# WattMeter_v4_I2C_Nov19_2018.net
KiCad netlist of a schematic drawn in EAGLE
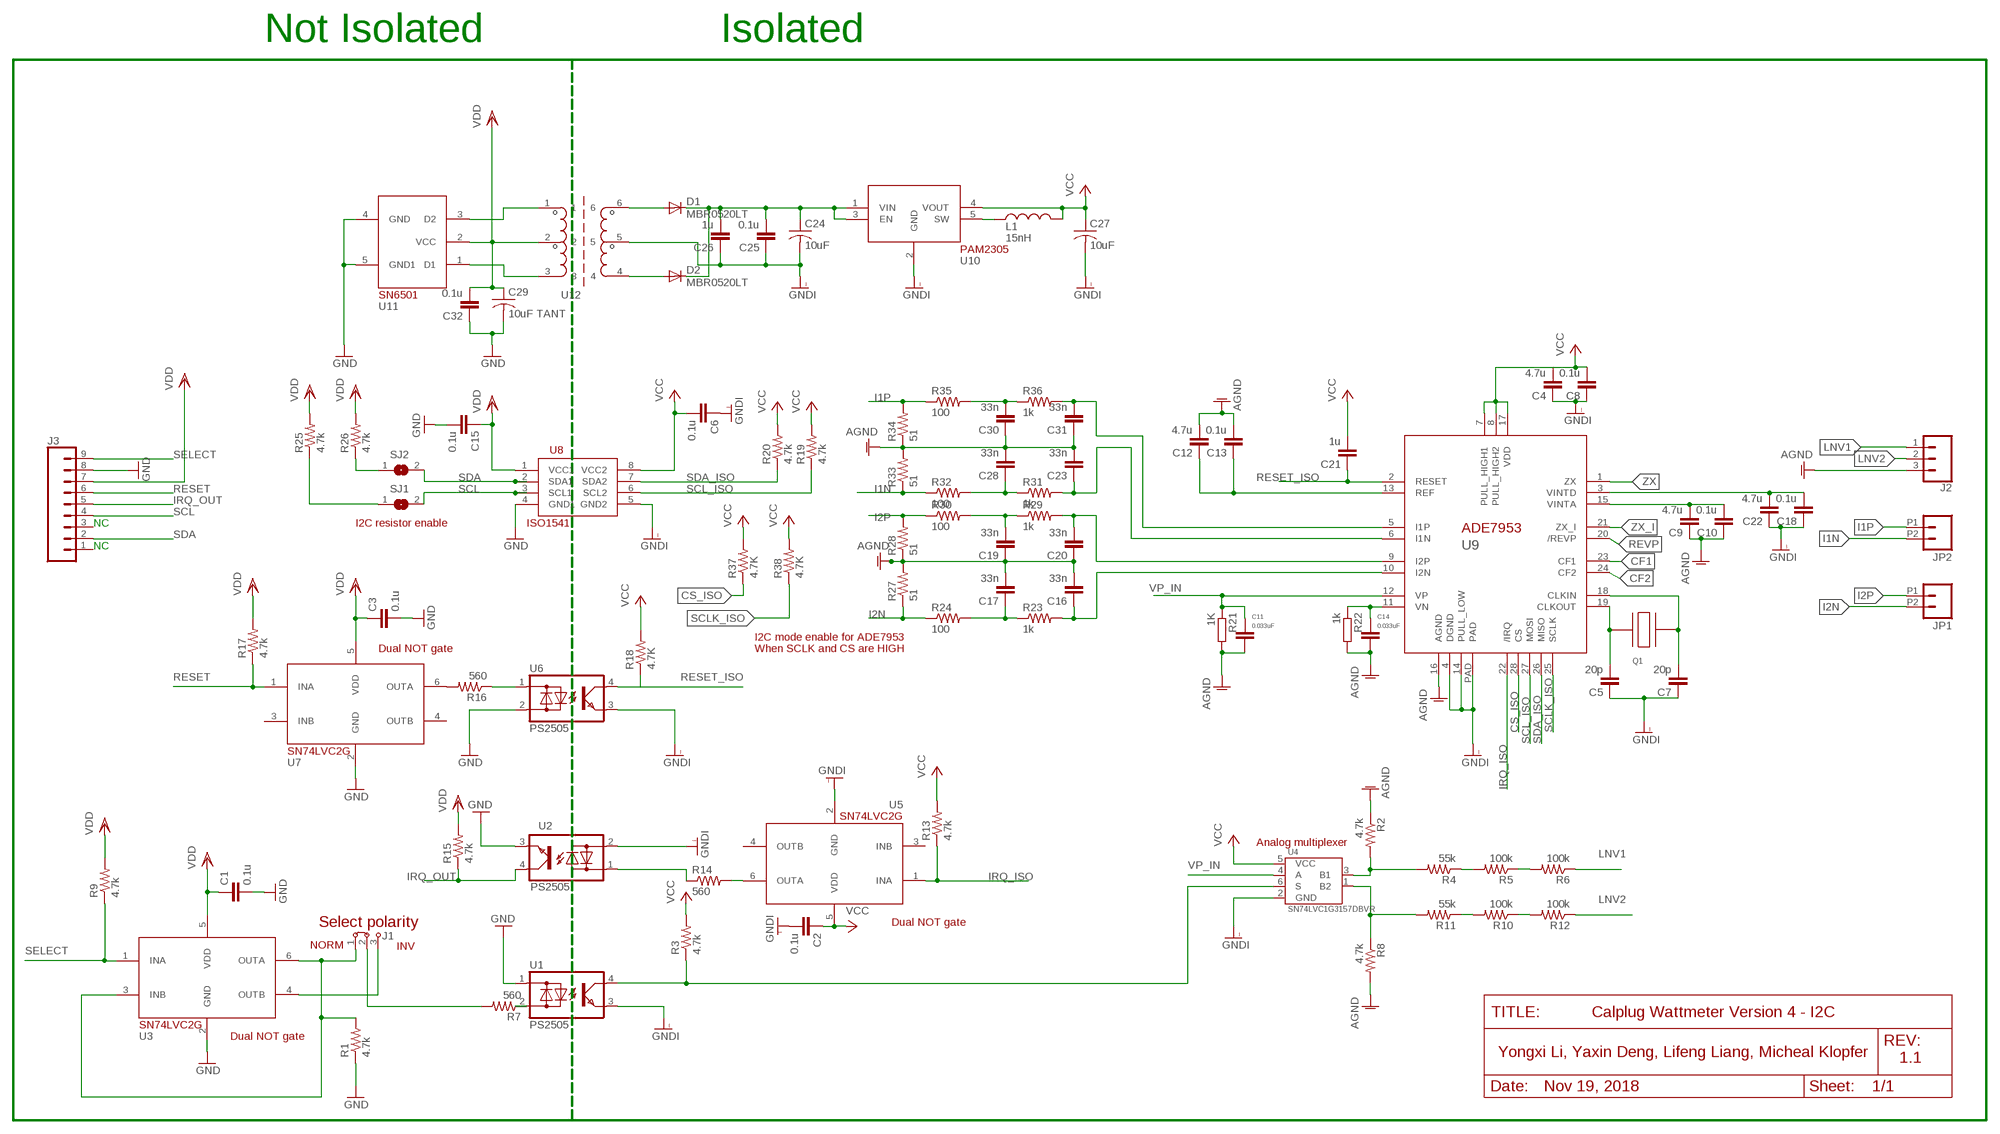
[diagram p0: schematic, sheet 1]

(export (version "E")
  (design (tool "Eeschema 10.0.6"))
  (components
    (comp (ref "C1")
      (value "0.1u")
      (footprint "eagle-import:0402-CAP")
      (libsource (lib "eagle-import") (part "0402-CAP"))
    )
    (comp (ref "C2")
      (value "0.1u")
      (footprint "eagle-import:0402-CAP")
      (libsource (lib "eagle-import") (part "0402-CAP"))
    )
    (comp (ref "C3")
      (value "0.1u")
      (footprint "eagle-import:0402-CAP")
      (libsource (lib "eagle-import") (part "0402-CAP"))
    )
    (comp (ref "C4")
      (value "4.7u")
      (footprint "eagle-import:0402-CAP")
      (libsource (lib "eagle-import") (part "0402-CAP"))
    )
    (comp (ref "C5")
      (value "20p")
      (footprint "eagle-import:0402-CAP")
      (libsource (lib "eagle-import") (part "0402-CAP"))
    )
    (comp (ref "C6")
      (value "0.1u")
      (footprint "eagle-import:0402-CAP")
      (libsource (lib "eagle-import") (part "0402-CAP"))
    )
    (comp (ref "C7")
      (value "20p")
      (footprint "eagle-import:0402-CAP")
      (libsource (lib "eagle-import") (part "0402-CAP"))
    )
    (comp (ref "C8")
      (value "0.1u")
      (footprint "eagle-import:0402-CAP")
      (libsource (lib "eagle-import") (part "0402-CAP"))
    )
    (comp (ref "C9")
      (value "4.7u")
      (footprint "eagle-import:0402-CAP")
      (libsource (lib "eagle-import") (part "0402-CAP"))
    )
    (comp (ref "C10")
      (value "0.1u")
      (footprint "eagle-import:0402-CAP")
      (libsource (lib "eagle-import") (part "0402-CAP"))
    )
    (comp (ref "C11")
      (value "0.033uF")
      (footprint "eagle-import:C0805K")
      (libsource (lib "eagle-import") (part "C-EUC0805K"))
    )
    (comp (ref "C12")
      (value "4.7u")
      (footprint "eagle-import:0402-CAP")
      (libsource (lib "eagle-import") (part "0402-CAP"))
    )
    (comp (ref "C13")
      (value "0.1u")
      (footprint "eagle-import:0402-CAP")
      (libsource (lib "eagle-import") (part "0402-CAP"))
    )
    (comp (ref "C14")
      (value "0.033uF")
      (footprint "eagle-import:C0805K")
      (libsource (lib "eagle-import") (part "C-EUC0805K"))
    )
    (comp (ref "C15")
      (value "0.1u")
      (footprint "eagle-import:0402-CAP")
      (libsource (lib "eagle-import") (part "0402-CAP"))
    )
    (comp (ref "C16")
      (value "33n")
      (footprint "eagle-import:0402-CAP")
      (libsource (lib "eagle-import") (part "0402-CAP"))
    )
    (comp (ref "C17")
      (value "33n")
      (footprint "eagle-import:0402-CAP")
      (libsource (lib "eagle-import") (part "0402-CAP"))
    )
    (comp (ref "C18")
      (value "0.1u")
      (footprint "eagle-import:0402-CAP")
      (libsource (lib "eagle-import") (part "0402-CAP"))
    )
    (comp (ref "C19")
      (value "33n")
      (footprint "eagle-import:0402-CAP")
      (libsource (lib "eagle-import") (part "0402-CAP"))
    )
    (comp (ref "C20")
      (value "33n")
      (footprint "eagle-import:0402-CAP")
      (libsource (lib "eagle-import") (part "0402-CAP"))
    )
    (comp (ref "C21")
      (value "1u")
      (footprint "eagle-import:0402-CAP")
      (libsource (lib "eagle-import") (part "0402-CAP"))
    )
    (comp (ref "C22")
      (value "4.7u")
      (footprint "eagle-import:0402-CAP")
      (libsource (lib "eagle-import") (part "0402-CAP"))
    )
    (comp (ref "C23")
      (value "33n")
      (footprint "eagle-import:0402-CAP")
      (libsource (lib "eagle-import") (part "0402-CAP"))
    )
    (comp (ref "C24")
      (value "10uF")
      (footprint "eagle-import:C0603")
      (libsource (lib "eagle-import") (part "C-USC0603"))
    )
    (comp (ref "C25")
      (value "0.1u")
      (footprint "eagle-import:0402-CAP")
      (libsource (lib "eagle-import") (part "0402-CAP"))
    )
    (comp (ref "C26")
      (value "1u")
      (footprint "eagle-import:0402-CAP")
      (libsource (lib "eagle-import") (part "0402-CAP"))
    )
    (comp (ref "C27")
      (value "10uF")
      (footprint "eagle-import:C0603")
      (libsource (lib "eagle-import") (part "C-USC0603"))
    )
    (comp (ref "C28")
      (value "33n")
      (footprint "eagle-import:0402-CAP")
      (libsource (lib "eagle-import") (part "0402-CAP"))
    )
    (comp (ref "C29")
      (value "10uF TANT")
      (footprint "eagle-import:C0603")
      (libsource (lib "eagle-import") (part "C-USC0603"))
    )
    (comp (ref "C30")
      (value "33n")
      (footprint "eagle-import:0402-CAP")
      (libsource (lib "eagle-import") (part "0402-CAP"))
    )
    (comp (ref "C31")
      (value "33n")
      (footprint "eagle-import:0402-CAP")
      (libsource (lib "eagle-import") (part "0402-CAP"))
    )
    (comp (ref "C32")
      (value "0.1u")
      (footprint "eagle-import:0402-CAP")
      (libsource (lib "eagle-import") (part "0402-CAP"))
    )
    (comp (ref "D1")
      (value "MBR0520LT")
      (footprint "eagle-import:SOD123")
      (libsource (lib "eagle-import") (part "MBR0520LT"))
    )
    (comp (ref "D2")
      (value "MBR0520LT")
      (footprint "eagle-import:SOD123")
      (libsource (lib "eagle-import") (part "MBR0520LT"))
    )
    (comp (ref "J1")
      (value "JUMPER3")
      (footprint "eagle-import:1X03")
      (libsource (lib "eagle-import") (part "JUMPER3"))
    )
    (comp (ref "J2")
      (value "CONN_03-SCREW-5MM")
      (footprint "eagle-import:SCREWTERMINAL-5MM-3")
      (libsource (lib "eagle-import") (part "CONN_03-SCREW-5MM"))
    )
    (comp (ref "J3")
      (value "CONN_09")
      (footprint "eagle-import:1X09")
      (libsource (lib "eagle-import") (part "CONN_09"))
    )
    (comp (ref "JP1")
      (value "M022.54MM_SCREWTERM")
      (footprint "eagle-import:1X02_2.54_SCREWTERM")
      (libsource (lib "eagle-import") (part "M022.54MM_SCREWTERM"))
    )
    (comp (ref "JP2")
      (value "M022.54MM_SCREWTERM")
      (footprint "eagle-import:1X02_2.54_SCREWTERM")
      (libsource (lib "eagle-import") (part "M022.54MM_SCREWTERM"))
    )
    (comp (ref "L1")
      (value "15nH")
      (footprint "eagle-import:0402-RES")
      (libsource (lib "eagle-import") (part "IND0402"))
    )
    (comp (ref "Q1")
      (value "QUARTZ_3.58M_2PIN")
      (footprint "eagle-import:HC-49S")
      (libsource (lib "eagle-import") (part "QUARTZ_3.58M_2PIN"))
    )
    (comp (ref "R1")
      (value "4.7k")
      (footprint "eagle-import:0402-RES")
      (libsource (lib "eagle-import") (part "0402-RES"))
    )
    (comp (ref "R2")
      (value "4.7k")
      (footprint "eagle-import:0603-RES")
      (libsource (lib "eagle-import") (part "RESISTOR0603-RES"))
    )
    (comp (ref "R3")
      (value "4.7k")
      (footprint "eagle-import:0402-RES")
      (libsource (lib "eagle-import") (part "0402-RES"))
    )
    (comp (ref "R4")
      (value "55k")
      (footprint "eagle-import:0603-RES")
      (libsource (lib "eagle-import") (part "RESISTOR0603-RES"))
    )
    (comp (ref "R5")
      (value "100k")
      (footprint "eagle-import:0603-RES")
      (libsource (lib "eagle-import") (part "RESISTOR0603-RES"))
    )
    (comp (ref "R6")
      (value "100k")
      (footprint "eagle-import:0603-RES")
      (libsource (lib "eagle-import") (part "RESISTOR0603-RES"))
    )
    (comp (ref "R7")
      (value "560")
      (footprint "eagle-import:0402-RES")
      (libsource (lib "eagle-import") (part "0402-RES"))
    )
    (comp (ref "R8")
      (value "4.7k")
      (footprint "eagle-import:0603-RES")
      (libsource (lib "eagle-import") (part "RESISTOR0603-RES"))
    )
    (comp (ref "R9")
      (value "4.7k")
      (footprint "eagle-import:0402-RES")
      (libsource (lib "eagle-import") (part "0402-RES"))
    )
    (comp (ref "R10")
      (value "100k")
      (footprint "eagle-import:0603-RES")
      (libsource (lib "eagle-import") (part "RESISTOR0603-RES"))
    )
    (comp (ref "R11")
      (value "55k")
      (footprint "eagle-import:0603-RES")
      (libsource (lib "eagle-import") (part "RESISTOR0603-RES"))
    )
    (comp (ref "R12")
      (value "100k")
      (footprint "eagle-import:0603-RES")
      (libsource (lib "eagle-import") (part "RESISTOR0603-RES"))
    )
    (comp (ref "R13")
      (value "4.7k")
      (footprint "eagle-import:0402-RES")
      (libsource (lib "eagle-import") (part "0402-RES"))
    )
    (comp (ref "R14")
      (value "560")
      (footprint "eagle-import:0402-RES")
      (libsource (lib "eagle-import") (part "0402-RES"))
    )
    (comp (ref "R15")
      (value "4.7k")
      (footprint "eagle-import:0402-RES")
      (libsource (lib "eagle-import") (part "0402-RES"))
    )
    (comp (ref "R16")
      (value "560")
      (footprint "eagle-import:0402-RES")
      (libsource (lib "eagle-import") (part "0402-RES"))
    )
    (comp (ref "R17")
      (value "4.7k")
      (footprint "eagle-import:0402-RES")
      (libsource (lib "eagle-import") (part "0402-RES"))
    )
    (comp (ref "R18")
      (value "4.7K")
      (footprint "eagle-import:0402-RES")
      (libsource (lib "eagle-import") (part "0402-RES"))
    )
    (comp (ref "R19")
      (value "4.7k")
      (footprint "eagle-import:0402-RES")
      (libsource (lib "eagle-import") (part "0402-RES"))
    )
    (comp (ref "R20")
      (value "4.7k")
      (footprint "eagle-import:0402-RES")
      (libsource (lib "eagle-import") (part "0402-RES"))
    )
    (comp (ref "R21")
      (value "1K")
      (footprint "eagle-import:C0805K@1")
      (libsource (lib "eagle-import") (part "R-EU_"))
    )
    (comp (ref "R22")
      (value "1k")
      (footprint "eagle-import:C0805K@1")
      (libsource (lib "eagle-import") (part "R-EU_"))
    )
    (comp (ref "R23")
      (value "1k")
      (footprint "eagle-import:0402-RES")
      (libsource (lib "eagle-import") (part "0402-RES"))
    )
    (comp (ref "R24")
      (value "100")
      (footprint "eagle-import:0402-RES")
      (libsource (lib "eagle-import") (part "0402-RES"))
    )
    (comp (ref "R25")
      (value "4.7k")
      (footprint "eagle-import:0402-RES")
      (libsource (lib "eagle-import") (part "0402-RES"))
    )
    (comp (ref "R26")
      (value "4.7k")
      (footprint "eagle-import:0402-RES")
      (libsource (lib "eagle-import") (part "0402-RES"))
    )
    (comp (ref "R27")
      (value "51")
      (footprint "eagle-import:0402-RES")
      (libsource (lib "eagle-import") (part "0402-RES"))
    )
    (comp (ref "R28")
      (value "51")
      (footprint "eagle-import:0402-RES")
      (libsource (lib "eagle-import") (part "0402-RES"))
    )
    (comp (ref "R29")
      (value "1k")
      (footprint "eagle-import:0402-RES")
      (libsource (lib "eagle-import") (part "0402-RES"))
    )
    (comp (ref "R30")
      (value "100")
      (footprint "eagle-import:0402-RES")
      (libsource (lib "eagle-import") (part "0402-RES"))
    )
    (comp (ref "R31")
      (value "1k")
      (footprint "eagle-import:0402-RES")
      (libsource (lib "eagle-import") (part "0402-RES"))
    )
    (comp (ref "R32")
      (value "100")
      (footprint "eagle-import:0402-RES")
      (libsource (lib "eagle-import") (part "0402-RES"))
    )
    (comp (ref "R33")
      (value "51")
      (footprint "eagle-import:0402-RES")
      (libsource (lib "eagle-import") (part "0402-RES"))
    )
    (comp (ref "R34")
      (value "51")
      (footprint "eagle-import:0402-RES")
      (libsource (lib "eagle-import") (part "0402-RES"))
    )
    (comp (ref "R35")
      (value "100")
      (footprint "eagle-import:0402-RES")
      (libsource (lib "eagle-import") (part "0402-RES"))
    )
    (comp (ref "R36")
      (value "1k")
      (footprint "eagle-import:0402-RES")
      (libsource (lib "eagle-import") (part "0402-RES"))
    )
    (comp (ref "R37")
      (value "4.7K")
      (footprint "eagle-import:0402-RES")
      (libsource (lib "eagle-import") (part "0402-RES"))
    )
    (comp (ref "R38")
      (value "4.7K")
      (footprint "eagle-import:0402-RES")
      (libsource (lib "eagle-import") (part "0402-RES"))
    )
    (comp (ref "SJ1") (value "SJ") (footprint "eagle-import:SJ") (libsource (lib "eagle-import") (part "SJ")))
    (comp (ref "SJ2") (value "SJ") (footprint "eagle-import:SJ") (libsource (lib "eagle-import") (part "SJ")))
    (comp (ref "U1")
      (value "PS2505")
      (footprint "eagle-import:PS2505")
      (libsource (lib "eagle-import") (part "PS2505"))
    )
    (comp (ref "U2")
      (value "PS2505")
      (footprint "eagle-import:PS2505")
      (libsource (lib "eagle-import") (part "PS2505"))
    )
    (comp (ref "U3")
      (value "SN74LVC")
      (footprint "eagle-import:DCKT")
      (libsource (lib "eagle-import") (part "SN74LVC"))
    )
    (comp (ref "U4")
      (value "SN74LVC1G3157DBVR")
      (footprint "eagle-import:SOT-23-6")
      (libsource (lib "eagle-import") (part "SN74LVC1G3157DBVR"))
    )
    (comp (ref "U5")
      (value "SN74LVC")
      (footprint "eagle-import:DCKT")
      (libsource (lib "eagle-import") (part "SN74LVC"))
    )
    (comp (ref "U6")
      (value "PS2505")
      (footprint "eagle-import:PS2505")
      (libsource (lib "eagle-import") (part "PS2505"))
    )
    (comp (ref "U7")
      (value "SN74LVC")
      (footprint "eagle-import:DCKT")
      (fields (field (name "SPICEPREFIX") "X"))
      (libsource (lib "eagle-import") (part "SN74LVC"))
    )
    (comp (ref "U8")
      (value "ISO1541")
      (footprint "eagle-import:ISO1541")
      (libsource (lib "eagle-import") (part "ISO1541"))
    )
    (comp (ref "U9")
      (value "ADE7953")
      (footprint "eagle-import:28-WFQFN")
      (libsource (lib "eagle-import") (part "ADE7953"))
    )
    (comp (ref "U10")
      (value "PAM2305")
      (footprint "eagle-import:TSOT25")
      (libsource (lib "eagle-import") (part "PAM2305"))
    )
    (comp (ref "U11")
      (value "SN6501")
      (footprint "eagle-import:SOT-23-5")
      (libsource (lib "eagle-import") (part "SN6501"))
    )
    (comp (ref "U12")
      (value "TRANSFO_3.3")
      (footprint "eagle-import:TRANSFO_3.3")
      (libsource (lib "eagle-import") (part "TRANSFO_3.3"))
    )
  )
  (nets
    (net (code "1") (name "/IRQ_ISO") (class "Default")
      (node (ref "R13") (pin "1") (pinfunction "1_1") (pintype "passive"))
      (node (ref "U5") (pin "1") (pinfunction "INA_1") (pintype "bidirectional"))
      (node (ref "U9") (pin "22") (pinfunction "/IRQ_22") (pintype "bidirectional"))
    )
    (net (code "2") (name "/IRQ_OUT") (class "Default")
      (node (ref "J3") (pin "5") (pinfunction "5_5") (pintype "passive"))
      (node (ref "R15") (pin "1") (pinfunction "1_1") (pintype "passive"))
      (node (ref "U2") (pin "4") (pinfunction "COLLERTOR_4") (pintype "passive"))
    )
    (net (code "3") (name "/RESET") (class "Default")
      (node (ref "J3") (pin "6") (pinfunction "6_6") (pintype "passive"))
      (node (ref "R17") (pin "1") (pinfunction "1_1") (pintype "passive"))
      (node (ref "U7") (pin "1") (pinfunction "INA_1") (pintype "bidirectional"))
    )
    (net (code "4") (name "/RESET_ISO") (class "Default")
      (node (ref "C21") (pin "1") (pinfunction "1_1") (pintype "passive"))
      (node (ref "R18") (pin "1") (pinfunction "1_1") (pintype "passive"))
      (node (ref "U6") (pin "4") (pinfunction "COLLERTOR_4") (pintype "passive"))
      (node (ref "U9") (pin "2") (pinfunction "RESET_2") (pintype "bidirectional"))
    )
    (net (code "5") (name "/SCL") (class "Default")
      (node (ref "J3") (pin "4") (pinfunction "4_4") (pintype "passive"))
      (node (ref "SJ1") (pin "2") (pinfunction "2_2") (pintype "passive"))
      (node (ref "U8") (pin "3") (pinfunction "SCL1_3") (pintype "bidirectional"))
    )
    (net (code "6") (name "/SCL_ISO") (class "Default")
      (node (ref "R19") (pin "1") (pinfunction "1_1") (pintype "passive"))
      (node (ref "U8") (pin "6") (pinfunction "SCL2_6") (pintype "bidirectional"))
      (node (ref "U9") (pin "27") (pinfunction "MOSI_27") (pintype "bidirectional"))
    )
    (net (code "7") (name "/SDA") (class "Default")
      (node (ref "J3") (pin "2") (pinfunction "2_2") (pintype "passive"))
      (node (ref "SJ2") (pin "2") (pinfunction "2_2") (pintype "passive"))
      (node (ref "U8") (pin "2") (pinfunction "SDA1_2") (pintype "bidirectional"))
    )
    (net (code "8") (name "/SDA_ISO") (class "Default")
      (node (ref "R20") (pin "1") (pinfunction "1_1") (pintype "passive"))
      (node (ref "U8") (pin "7") (pinfunction "SDA2_7") (pintype "bidirectional"))
      (node (ref "U9") (pin "26") (pinfunction "MISO_26") (pintype "bidirectional"))
    )
    (net (code "9") (name "/SELECT") (class "Default")
      (node (ref "J3") (pin "9") (pinfunction "9_9") (pintype "passive"))
      (node (ref "R9") (pin "1") (pinfunction "1_1") (pintype "passive"))
      (node (ref "U3") (pin "1") (pinfunction "INA_1") (pintype "bidirectional"))
    )
    (net (code "10") (name "/VP_IN") (class "Default")
      (node (ref "C11") (pin "1") (pinfunction "1_1") (pintype "passive"))
      (node (ref "R21") (pin "1") (pinfunction "1_1") (pintype "passive"))
      (node (ref "U4") (pin "4") (pinfunction "A_4") (pintype "bidirectional"))
      (node (ref "U9") (pin "12") (pinfunction "VP_12") (pintype "bidirectional"))
    )
    (net (code "11") (name "AGND") (class "Default")
      (node (ref "C10") (pin "1") (pinfunction "1_1") (pintype "passive"))
      (node (ref "C11") (pin "2") (pinfunction "2_2") (pintype "passive"))
      (node (ref "C12") (pin "2") (pinfunction "2_2") (pintype "passive"))
      (node (ref "C13") (pin "2") (pinfunction "2_2") (pintype "passive"))
      (node (ref "C14") (pin "2") (pinfunction "2_2") (pintype "passive"))
      (node (ref "C16") (pin "2") (pinfunction "2_2") (pintype "passive"))
      (node (ref "C17") (pin "2") (pinfunction "2_2") (pintype "passive"))
      (node (ref "C19") (pin "1") (pinfunction "1_1") (pintype "passive"))
      (node (ref "C20") (pin "1") (pinfunction "1_1") (pintype "passive"))
      (node (ref "C23") (pin "2") (pinfunction "2_2") (pintype "passive"))
      (node (ref "C28") (pin "2") (pinfunction "2_2") (pintype "passive"))
      (node (ref "C30") (pin "1") (pinfunction "1_1") (pintype "passive"))
      (node (ref "C31") (pin "1") (pinfunction "1_1") (pintype "passive"))
      (node (ref "C9") (pin "1") (pinfunction "1_1") (pintype "passive"))
      (node (ref "J2") (pin "3") (pinfunction "3_3") (pintype "passive"))
      (node (ref "R2") (pin "1") (pinfunction "1_1") (pintype "passive"))
      (node (ref "R21") (pin "2") (pinfunction "2_2") (pintype "passive"))
      (node (ref "R22") (pin "2") (pinfunction "2_2") (pintype "passive"))
      (node (ref "R27") (pin "2") (pinfunction "2_2") (pintype "passive"))
      (node (ref "R28") (pin "1") (pinfunction "1_1") (pintype "passive"))
      (node (ref "R33") (pin "2") (pinfunction "2_2") (pintype "passive"))
      (node (ref "R34") (pin "1") (pinfunction "1_1") (pintype "passive"))
      (node (ref "R8") (pin "2") (pinfunction "2_2") (pintype "passive"))
      (node (ref "U9") (pin "16") (pinfunction "AGND_16") (pintype "bidirectional"))
    )
    (net (code "12") (name "CF1") (class "Default")
      (node (ref "U9") (pin "23") (pinfunction "CF1_23") (pintype "bidirectional"))
    )
    (net (code "13") (name "CF2") (class "Default")
      (node (ref "U9") (pin "24") (pinfunction "CF2_24") (pintype "bidirectional"))
    )
    (net (code "14") (name "CS_ISO") (class "Default")
      (node (ref "R37") (pin "1") (pinfunction "1_1") (pintype "passive"))
      (node (ref "U9") (pin "28") (pinfunction "CS_28") (pintype "bidirectional"))
    )
    (net (code "15") (name "GND") (class "Default")
      (node (ref "C1") (pin "2") (pinfunction "2_2") (pintype "passive"))
      (node (ref "C15") (pin "2") (pinfunction "2_2") (pintype "passive"))
      (node (ref "C29") (pin "2") (pinfunction "2_2") (pintype "passive"))
      (node (ref "C3") (pin "2") (pinfunction "2_2") (pintype "passive"))
      (node (ref "C32") (pin "1") (pinfunction "1_1") (pintype "passive"))
      (node (ref "J3") (pin "8") (pinfunction "8_8") (pintype "passive"))
      (node (ref "R1") (pin "1") (pinfunction "1_1") (pintype "passive"))
      (node (ref "U1") (pin "1") (pinfunction "ANODE_1") (pintype "passive"))
      (node (ref "U11") (pin "4") (pinfunction "GND_4") (pintype "bidirectional"))
      (node (ref "U11") (pin "5") (pinfunction "GND1_5") (pintype "bidirectional"))
      (node (ref "U2") (pin "3") (pinfunction "EMITTER_3") (pintype "passive"))
      (node (ref "U3") (pin "2") (pinfunction "GND_2") (pintype "bidirectional"))
      (node (ref "U6") (pin "2") (pinfunction "CATHODE_2") (pintype "passive"))
      (node (ref "U7") (pin "2") (pinfunction "GND_2") (pintype "bidirectional"))
      (node (ref "U8") (pin "4") (pinfunction "GND1_4") (pintype "bidirectional"))
    )
    (net (code "16") (name "GNDI") (class "Default")
      (node (ref "C18") (pin "1") (pinfunction "1_1") (pintype "passive"))
      (node (ref "C2") (pin "2") (pinfunction "2_2") (pintype "passive"))
      (node (ref "C22") (pin "1") (pinfunction "1_1") (pintype "passive"))
      (node (ref "C24") (pin "2") (pinfunction "2_2") (pintype "passive"))
      (node (ref "C25") (pin "1") (pinfunction "1_1") (pintype "passive"))
      (node (ref "C26") (pin "1") (pinfunction "1_1") (pintype "passive"))
      (node (ref "C27") (pin "2") (pinfunction "2_2") (pintype "passive"))
      (node (ref "C4") (pin "1") (pinfunction "1_1") (pintype "passive"))
      (node (ref "C5") (pin "1") (pinfunction "1_1") (pintype "passive"))
      (node (ref "C6") (pin "1") (pinfunction "1_1") (pintype "passive"))
      (node (ref "C7") (pin "1") (pinfunction "1_1") (pintype "passive"))
      (node (ref "C8") (pin "1") (pinfunction "1_1") (pintype "passive"))
      (node (ref "U1") (pin "3") (pinfunction "EMITTER_3") (pintype "passive"))
      (node (ref "U10") (pin "2") (pinfunction "GND_2") (pintype "bidirectional"))
      (node (ref "U12") (pin "5") (pinfunction "5_5") (pintype "bidirectional"))
      (node (ref "U2") (pin "2") (pinfunction "CATHODE_2") (pintype "passive"))
      (node (ref "U4") (pin "2") (pinfunction "GND_2") (pintype "bidirectional"))
      (node (ref "U5") (pin "2") (pinfunction "GND_2") (pintype "bidirectional"))
      (node (ref "U6") (pin "3") (pinfunction "EMITTER_3") (pintype "passive"))
      (node (ref "U8") (pin "5") (pinfunction "GND2_5") (pintype "bidirectional"))
      (node (ref "U9") (pin "14") (pinfunction "PULL_LOW_14") (pintype "bidirectional"))
      (node (ref "U9") (pin "4") (pinfunction "DGND_4") (pintype "bidirectional"))
      (node (ref "U9") (pin "PAD") (pinfunction "PAD_PAD") (pintype "bidirectional"))
    )
    (net (code "17") (name "I1N") (class "Default")
      (node (ref "JP2") (pin "P2") (pinfunction "2_P2") (pintype "passive"))
      (node (ref "R32") (pin "1") (pinfunction "1_1") (pintype "passive"))
      (node (ref "R33") (pin "1") (pinfunction "1_1") (pintype "passive"))
    )
    (net (code "18") (name "I1P") (class "Default")
      (node (ref "JP2") (pin "P1") (pinfunction "1_P1") (pintype "passive"))
      (node (ref "R34") (pin "2") (pinfunction "2_2") (pintype "passive"))
      (node (ref "R35") (pin "1") (pinfunction "1_1") (pintype "passive"))
    )
    (net (code "19") (name "I2N") (class "Default")
      (node (ref "JP1") (pin "P2") (pinfunction "2_P2") (pintype "passive"))
      (node (ref "R24") (pin "1") (pinfunction "1_1") (pintype "passive"))
      (node (ref "R27") (pin "1") (pinfunction "1_1") (pintype "passive"))
    )
    (net (code "20") (name "I2P") (class "Default")
      (node (ref "JP1") (pin "P1") (pinfunction "1_P1") (pintype "passive"))
      (node (ref "R28") (pin "2") (pinfunction "2_2") (pintype "passive"))
      (node (ref "R30") (pin "1") (pinfunction "1_1") (pintype "passive"))
    )
    (net (code "21") (name "LNV1") (class "Default")
      (node (ref "J2") (pin "1") (pinfunction "1_1") (pintype "passive"))
      (node (ref "R6") (pin "1") (pinfunction "1_1") (pintype "passive"))
    )
    (net (code "22") (name "LNV2") (class "Default")
      (node (ref "J2") (pin "2") (pinfunction "2_2") (pintype "passive"))
      (node (ref "R12") (pin "1") (pinfunction "1_1") (pintype "passive"))
    )
    (net (code "23") (name "Net-(C17-Pad1)") (class "Default")
      (node (ref "C17") (pin "1") (pinfunction "1_1") (pintype "passive"))
      (node (ref "R23") (pin "1") (pinfunction "1_1") (pintype "passive"))
      (node (ref "R24") (pin "2") (pinfunction "2_2") (pintype "passive"))
    )
    (net (code "24") (name "Net-(C19-Pad2)") (class "Default")
      (node (ref "C19") (pin "2") (pinfunction "2_2") (pintype "passive"))
      (node (ref "R29") (pin "1") (pinfunction "1_1") (pintype "passive"))
      (node (ref "R30") (pin "2") (pinfunction "2_2") (pintype "passive"))
    )
    (net (code "25") (name "Net-(C28-Pad1)") (class "Default")
      (node (ref "C28") (pin "1") (pinfunction "1_1") (pintype "passive"))
      (node (ref "R31") (pin "1") (pinfunction "1_1") (pintype "passive"))
      (node (ref "R32") (pin "2") (pinfunction "2_2") (pintype "passive"))
    )
    (net (code "26") (name "Net-(C30-Pad2)") (class "Default")
      (node (ref "C30") (pin "2") (pinfunction "2_2") (pintype "passive"))
      (node (ref "R35") (pin "2") (pinfunction "2_2") (pintype "passive"))
      (node (ref "R36") (pin "1") (pinfunction "1_1") (pintype "passive"))
    )
    (net (code "27") (name "Net-(D1-PadA)") (class "Default")
      (node (ref "D1") (pin "A") (pinfunction "A_A") (pintype "passive"))
      (node (ref "U12") (pin "6") (pinfunction "6_6") (pintype "bidirectional"))
    )
    (net (code "28") (name "Net-(D2-PadA)") (class "Default")
      (node (ref "D2") (pin "A") (pinfunction "A_A") (pintype "passive"))
      (node (ref "U12") (pin "4") (pinfunction "4_4") (pintype "bidirectional"))
    )
    (net (code "29") (name "Net-(J1-Pad2)") (class "Default")
      (node (ref "J1") (pin "2") (pinfunction "2_2") (pintype "passive"))
      (node (ref "R7") (pin "2") (pinfunction "2_2") (pintype "passive"))
    )
    (net (code "30") (name "Net-(R4-Pad1)") (class "Default")
      (node (ref "R4") (pin "1") (pinfunction "1_1") (pintype "passive"))
      (node (ref "R5") (pin "2") (pinfunction "2_2") (pintype "passive"))
    )
    (net (code "31") (name "Net-(R5-Pad1)") (class "Default")
      (node (ref "R5") (pin "1") (pinfunction "1_1") (pintype "passive"))
      (node (ref "R6") (pin "2") (pinfunction "2_2") (pintype "passive"))
    )
    (net (code "32") (name "Net-(R10-Pad1)") (class "Default")
      (node (ref "R10") (pin "1") (pinfunction "1_1") (pintype "passive"))
      (node (ref "R12") (pin "2") (pinfunction "2_2") (pintype "passive"))
    )
    (net (code "33") (name "Net-(R10-Pad2)") (class "Default")
      (node (ref "R10") (pin "2") (pinfunction "2_2") (pintype "passive"))
      (node (ref "R11") (pin "1") (pinfunction "1_1") (pintype "passive"))
    )
    (net (code "34") (name "Net-(R25-Pad1)") (class "Default")
      (node (ref "R25") (pin "1") (pinfunction "1_1") (pintype "passive"))
      (node (ref "SJ1") (pin "1") (pinfunction "1_1") (pintype "passive"))
    )
    (net (code "35") (name "Net-(R26-Pad1)") (class "Default")
      (node (ref "R26") (pin "1") (pinfunction "1_1") (pintype "passive"))
      (node (ref "SJ2") (pin "1") (pinfunction "1_1") (pintype "passive"))
    )
    (net (code "36") (name "Net-(U1-CATHODE)") (class "Default")
      (node (ref "R7") (pin "1") (pinfunction "1_1") (pintype "passive"))
      (node (ref "U1") (pin "2") (pinfunction "CATHODE_2") (pintype "passive"))
    )
    (net (code "37") (name "Net-(U1-COLLERTOR)") (class "Default")
      (node (ref "R3") (pin "1") (pinfunction "1_1") (pintype "passive"))
      (node (ref "U1") (pin "4") (pinfunction "COLLERTOR_4") (pintype "passive"))
      (node (ref "U4") (pin "6") (pinfunction "S_6") (pintype "bidirectional"))
    )
    (net (code "38") (name "Net-(U2-ANODE)") (class "Default")
      (node (ref "R14") (pin "1") (pinfunction "1_1") (pintype "passive"))
      (node (ref "U2") (pin "1") (pinfunction "ANODE_1") (pintype "passive"))
    )
    (net (code "39") (name "Net-(U3-INB)") (class "Default")
      (node (ref "J1") (pin "1") (pinfunction "1_1") (pintype "passive"))
      (node (ref "R1") (pin "2") (pinfunction "2_2") (pintype "passive"))
      (node (ref "U3") (pin "3") (pinfunction "INB_3") (pintype "bidirectional"))
      (node (ref "U3") (pin "6") (pinfunction "OUTA_6") (pintype "bidirectional"))
    )
    (net (code "40") (name "Net-(U3-OUTB)") (class "Default")
      (node (ref "J1") (pin "3") (pinfunction "3_3") (pintype "passive"))
      (node (ref "U3") (pin "4") (pinfunction "OUTB_4") (pintype "bidirectional"))
    )
    (net (code "41") (name "Net-(U4-B1)") (class "Default")
      (node (ref "R2") (pin "2") (pinfunction "2_2") (pintype "passive"))
      (node (ref "R4") (pin "2") (pinfunction "2_2") (pintype "passive"))
      (node (ref "U4") (pin "3") (pinfunction "B1_3") (pintype "bidirectional"))
    )
    (net (code "42") (name "Net-(U4-B2)") (class "Default")
      (node (ref "R11") (pin "2") (pinfunction "2_2") (pintype "passive"))
      (node (ref "R8") (pin "1") (pinfunction "1_1") (pintype "passive"))
      (node (ref "U4") (pin "1") (pinfunction "B2_1") (pintype "bidirectional"))
    )
    (net (code "43") (name "Net-(U5-OUTA)") (class "Default")
      (node (ref "R14") (pin "2") (pinfunction "2_2") (pintype "passive"))
      (node (ref "U5") (pin "6") (pinfunction "OUTA_6") (pintype "bidirectional"))
    )
    (net (code "44") (name "Net-(U6-ANODE)") (class "Default")
      (node (ref "R16") (pin "1") (pinfunction "1_1") (pintype "passive"))
      (node (ref "U6") (pin "1") (pinfunction "ANODE_1") (pintype "passive"))
    )
    (net (code "45") (name "Net-(U7-OUTA)") (class "Default")
      (node (ref "R16") (pin "2") (pinfunction "2_2") (pintype "passive"))
      (node (ref "U7") (pin "6") (pinfunction "OUTA_6") (pintype "bidirectional"))
    )
    (net (code "46") (name "Net-(U9-CLKIN)") (class "Default")
      (node (ref "C7") (pin "2") (pinfunction "2_2") (pintype "passive"))
      (node (ref "Q1") (pin "2") (pinfunction "2_2") (pintype "bidirectional"))
      (node (ref "U9") (pin "18") (pinfunction "CLKIN_18") (pintype "bidirectional"))
    )
    (net (code "47") (name "Net-(U9-CLKOUT)") (class "Default")
      (node (ref "C5") (pin "2") (pinfunction "2_2") (pintype "passive"))
      (node (ref "Q1") (pin "1") (pinfunction "1_1") (pintype "bidirectional"))
      (node (ref "U9") (pin "19") (pinfunction "CLKOUT_19") (pintype "bidirectional"))
    )
    (net (code "48") (name "Net-(U9-I1N)") (class "Default")
      (node (ref "C23") (pin "1") (pinfunction "1_1") (pintype "passive"))
      (node (ref "R31") (pin "2") (pinfunction "2_2") (pintype "passive"))
      (node (ref "U9") (pin "6") (pinfunction "I1N_6") (pintype "bidirectional"))
    )
    (net (code "49") (name "Net-(U9-I1P)") (class "Default")
      (node (ref "C31") (pin "2") (pinfunction "2_2") (pintype "passive"))
      (node (ref "R36") (pin "2") (pinfunction "2_2") (pintype "passive"))
      (node (ref "U9") (pin "5") (pinfunction "I1P_5") (pintype "bidirectional"))
    )
    (net (code "50") (name "Net-(U9-I2N)") (class "Default")
      (node (ref "C16") (pin "1") (pinfunction "1_1") (pintype "passive"))
      (node (ref "R23") (pin "2") (pinfunction "2_2") (pintype "passive"))
      (node (ref "U9") (pin "10") (pinfunction "I2N_10") (pintype "bidirectional"))
    )
    (net (code "51") (name "Net-(U9-I2P)") (class "Default")
      (node (ref "C20") (pin "2") (pinfunction "2_2") (pintype "passive"))
      (node (ref "R29") (pin "2") (pinfunction "2_2") (pintype "passive"))
      (node (ref "U9") (pin "9") (pinfunction "I2P_9") (pintype "bidirectional"))
    )
    (net (code "52") (name "Net-(U9-REF)") (class "Default")
      (node (ref "C12") (pin "1") (pinfunction "1_1") (pintype "passive"))
      (node (ref "C13") (pin "1") (pinfunction "1_1") (pintype "passive"))
      (node (ref "U9") (pin "13") (pinfunction "REF_13") (pintype "bidirectional"))
    )
    (net (code "53") (name "Net-(U9-VINTA)") (class "Default")
      (node (ref "C10") (pin "2") (pinfunction "2_2") (pintype "passive"))
      (node (ref "C9") (pin "2") (pinfunction "2_2") (pintype "passive"))
      (node (ref "U9") (pin "15") (pinfunction "VINTA_15") (pintype "bidirectional"))
    )
    (net (code "54") (name "Net-(U9-VINTD)") (class "Default")
      (node (ref "C18") (pin "2") (pinfunction "2_2") (pintype "passive"))
      (node (ref "C22") (pin "2") (pinfunction "2_2") (pintype "passive"))
      (node (ref "U9") (pin "3") (pinfunction "VINTD_3") (pintype "bidirectional"))
    )
    (net (code "55") (name "Net-(U9-VN)") (class "Default")
      (node (ref "C14") (pin "1") (pinfunction "1_1") (pintype "passive"))
      (node (ref "R22") (pin "1") (pinfunction "1_1") (pintype "passive"))
      (node (ref "U9") (pin "11") (pinfunction "VN_11") (pintype "bidirectional"))
    )
    (net (code "56") (name "Net-(U10-EN)") (class "Default")
      (node (ref "C24") (pin "1") (pinfunction "1_1") (pintype "passive"))
      (node (ref "C25") (pin "2") (pinfunction "2_2") (pintype "passive"))
      (node (ref "C26") (pin "2") (pinfunction "2_2") (pintype "passive"))
      (node (ref "D1") (pin "C") (pinfunction "C_C") (pintype "passive"))
      (node (ref "D2") (pin "C") (pinfunction "C_C") (pintype "passive"))
      (node (ref "U10") (pin "1") (pinfunction "VIN_1") (pintype "bidirectional"))
      (node (ref "U10") (pin "3") (pinfunction "EN_3") (pintype "bidirectional"))
    )
    (net (code "57") (name "Net-(U10-SW)") (class "Default")
      (node (ref "L1") (pin "1") (pinfunction "1_1") (pintype "bidirectional"))
      (node (ref "U10") (pin "5") (pinfunction "SW_5") (pintype "bidirectional"))
    )
    (net (code "58") (name "Net-(U11-D1)") (class "Default")
      (node (ref "U11") (pin "1") (pinfunction "D1_1") (pintype "bidirectional"))
      (node (ref "U12") (pin "3") (pinfunction "3_3") (pintype "bidirectional"))
    )
    (net (code "59") (name "Net-(U11-D2)") (class "Default")
      (node (ref "U11") (pin "3") (pinfunction "D2_3") (pintype "bidirectional"))
      (node (ref "U12") (pin "1") (pinfunction "1_1") (pintype "bidirectional"))
    )
    (net (code "60") (name "REVP") (class "Default")
      (node (ref "U9") (pin "20") (pinfunction "/REVP_20") (pintype "bidirectional"))
    )
    (net (code "61") (name "SCLK_ISO") (class "Default")
      (node (ref "R38") (pin "1") (pinfunction "1_1") (pintype "passive"))
      (node (ref "U9") (pin "25") (pinfunction "SCLK_25") (pintype "bidirectional"))
    )
    (net (code "62") (name "VCC") (class "Default")
      (node (ref "C2") (pin "1") (pinfunction "1_1") (pintype "passive"))
      (node (ref "C21") (pin "2") (pinfunction "2_2") (pintype "passive"))
      (node (ref "C27") (pin "1") (pinfunction "1_1") (pintype "passive"))
      (node (ref "C4") (pin "2") (pinfunction "2_2") (pintype "passive"))
      (node (ref "C6") (pin "2") (pinfunction "2_2") (pintype "passive"))
      (node (ref "C8") (pin "2") (pinfunction "2_2") (pintype "passive"))
      (node (ref "L1") (pin "2") (pinfunction "2_2") (pintype "bidirectional"))
      (node (ref "R13") (pin "2") (pinfunction "2_2") (pintype "passive"))
      (node (ref "R18") (pin "2") (pinfunction "2_2") (pintype "passive"))
      (node (ref "R19") (pin "2") (pinfunction "2_2") (pintype "passive"))
      (node (ref "R20") (pin "2") (pinfunction "2_2") (pintype "passive"))
      (node (ref "R3") (pin "2") (pinfunction "2_2") (pintype "passive"))
      (node (ref "R37") (pin "2") (pinfunction "2_2") (pintype "passive"))
      (node (ref "R38") (pin "2") (pinfunction "2_2") (pintype "passive"))
      (node (ref "U10") (pin "4") (pinfunction "VOUT_4") (pintype "bidirectional"))
      (node (ref "U4") (pin "5") (pinfunction "VCC_5") (pintype "bidirectional"))
      (node (ref "U5") (pin "5") (pinfunction "VDD_5") (pintype "bidirectional"))
      (node (ref "U8") (pin "8") (pinfunction "VCC2_8") (pintype "bidirectional"))
      (node (ref "U9") (pin "17") (pinfunction "VDD_17") (pintype "bidirectional"))
      (node (ref "U9") (pin "7") (pinfunction "PULL_HIGH1_7") (pintype "bidirectional"))
      (node (ref "U9") (pin "8") (pinfunction "PULL_HIGH2_8") (pintype "bidirectional"))
    )
    (net (code "63") (name "VDD") (class "Default")
      (node (ref "C1") (pin "1") (pinfunction "1_1") (pintype "passive"))
      (node (ref "C15") (pin "1") (pinfunction "1_1") (pintype "passive"))
      (node (ref "C29") (pin "1") (pinfunction "1_1") (pintype "passive"))
      (node (ref "C3") (pin "1") (pinfunction "1_1") (pintype "passive"))
      (node (ref "C32") (pin "2") (pinfunction "2_2") (pintype "passive"))
      (node (ref "J3") (pin "7") (pinfunction "7_7") (pintype "passive"))
      (node (ref "R15") (pin "2") (pinfunction "2_2") (pintype "passive"))
      (node (ref "R17") (pin "2") (pinfunction "2_2") (pintype "passive"))
      (node (ref "R25") (pin "2") (pinfunction "2_2") (pintype "passive"))
      (node (ref "R26") (pin "2") (pinfunction "2_2") (pintype "passive"))
      (node (ref "R9") (pin "2") (pinfunction "2_2") (pintype "passive"))
      (node (ref "U11") (pin "2") (pinfunction "VCC_2") (pintype "bidirectional"))
      (node (ref "U12") (pin "2") (pinfunction "2_2") (pintype "bidirectional"))
      (node (ref "U3") (pin "5") (pinfunction "VDD_5") (pintype "bidirectional"))
      (node (ref "U7") (pin "5") (pinfunction "VDD_5") (pintype "bidirectional"))
      (node (ref "U8") (pin "1") (pinfunction "VCC1_1") (pintype "bidirectional"))
    )
    (net (code "64") (name "ZX") (class "Default")
      (node (ref "U9") (pin "1") (pinfunction "ZX_1") (pintype "bidirectional"))
    )
    (net (code "65") (name "ZX_I") (class "Default")
      (node (ref "U9") (pin "21") (pinfunction "ZX_I_21") (pintype "bidirectional"))
    )
    (net (code "66") (name "unconnected-(J3-Pad1)") (class "Default")
      (node (ref "J3") (pin "1") (pinfunction "1_1") (pintype "passive"))
    )
    (net (code "67") (name "unconnected-(J3-Pad3)") (class "Default")
      (node (ref "J3") (pin "3") (pinfunction "3_3") (pintype "passive"))
    )
    (net (code "68") (name "unconnected-(U5-INB-Pad3)") (class "Default")
      (node (ref "U5") (pin "3") (pinfunction "INB_3") (pintype "bidirectional"))
    )
    (net (code "69") (name "unconnected-(U5-OUTB-Pad4)") (class "Default")
      (node (ref "U5") (pin "4") (pinfunction "OUTB_4") (pintype "bidirectional"))
    )
    (net (code "70") (name "unconnected-(U7-INB-Pad3)") (class "Default")
      (node (ref "U7") (pin "3") (pinfunction "INB_3") (pintype "bidirectional"))
    )
    (net (code "71") (name "unconnected-(U7-OUTB-Pad4)") (class "Default")
      (node (ref "U7") (pin "4") (pinfunction "OUTB_4") (pintype "bidirectional"))
    )
  )
)
